# pcb1.net
KiCad netlist of a schematic drawn in EasyEDA Pro
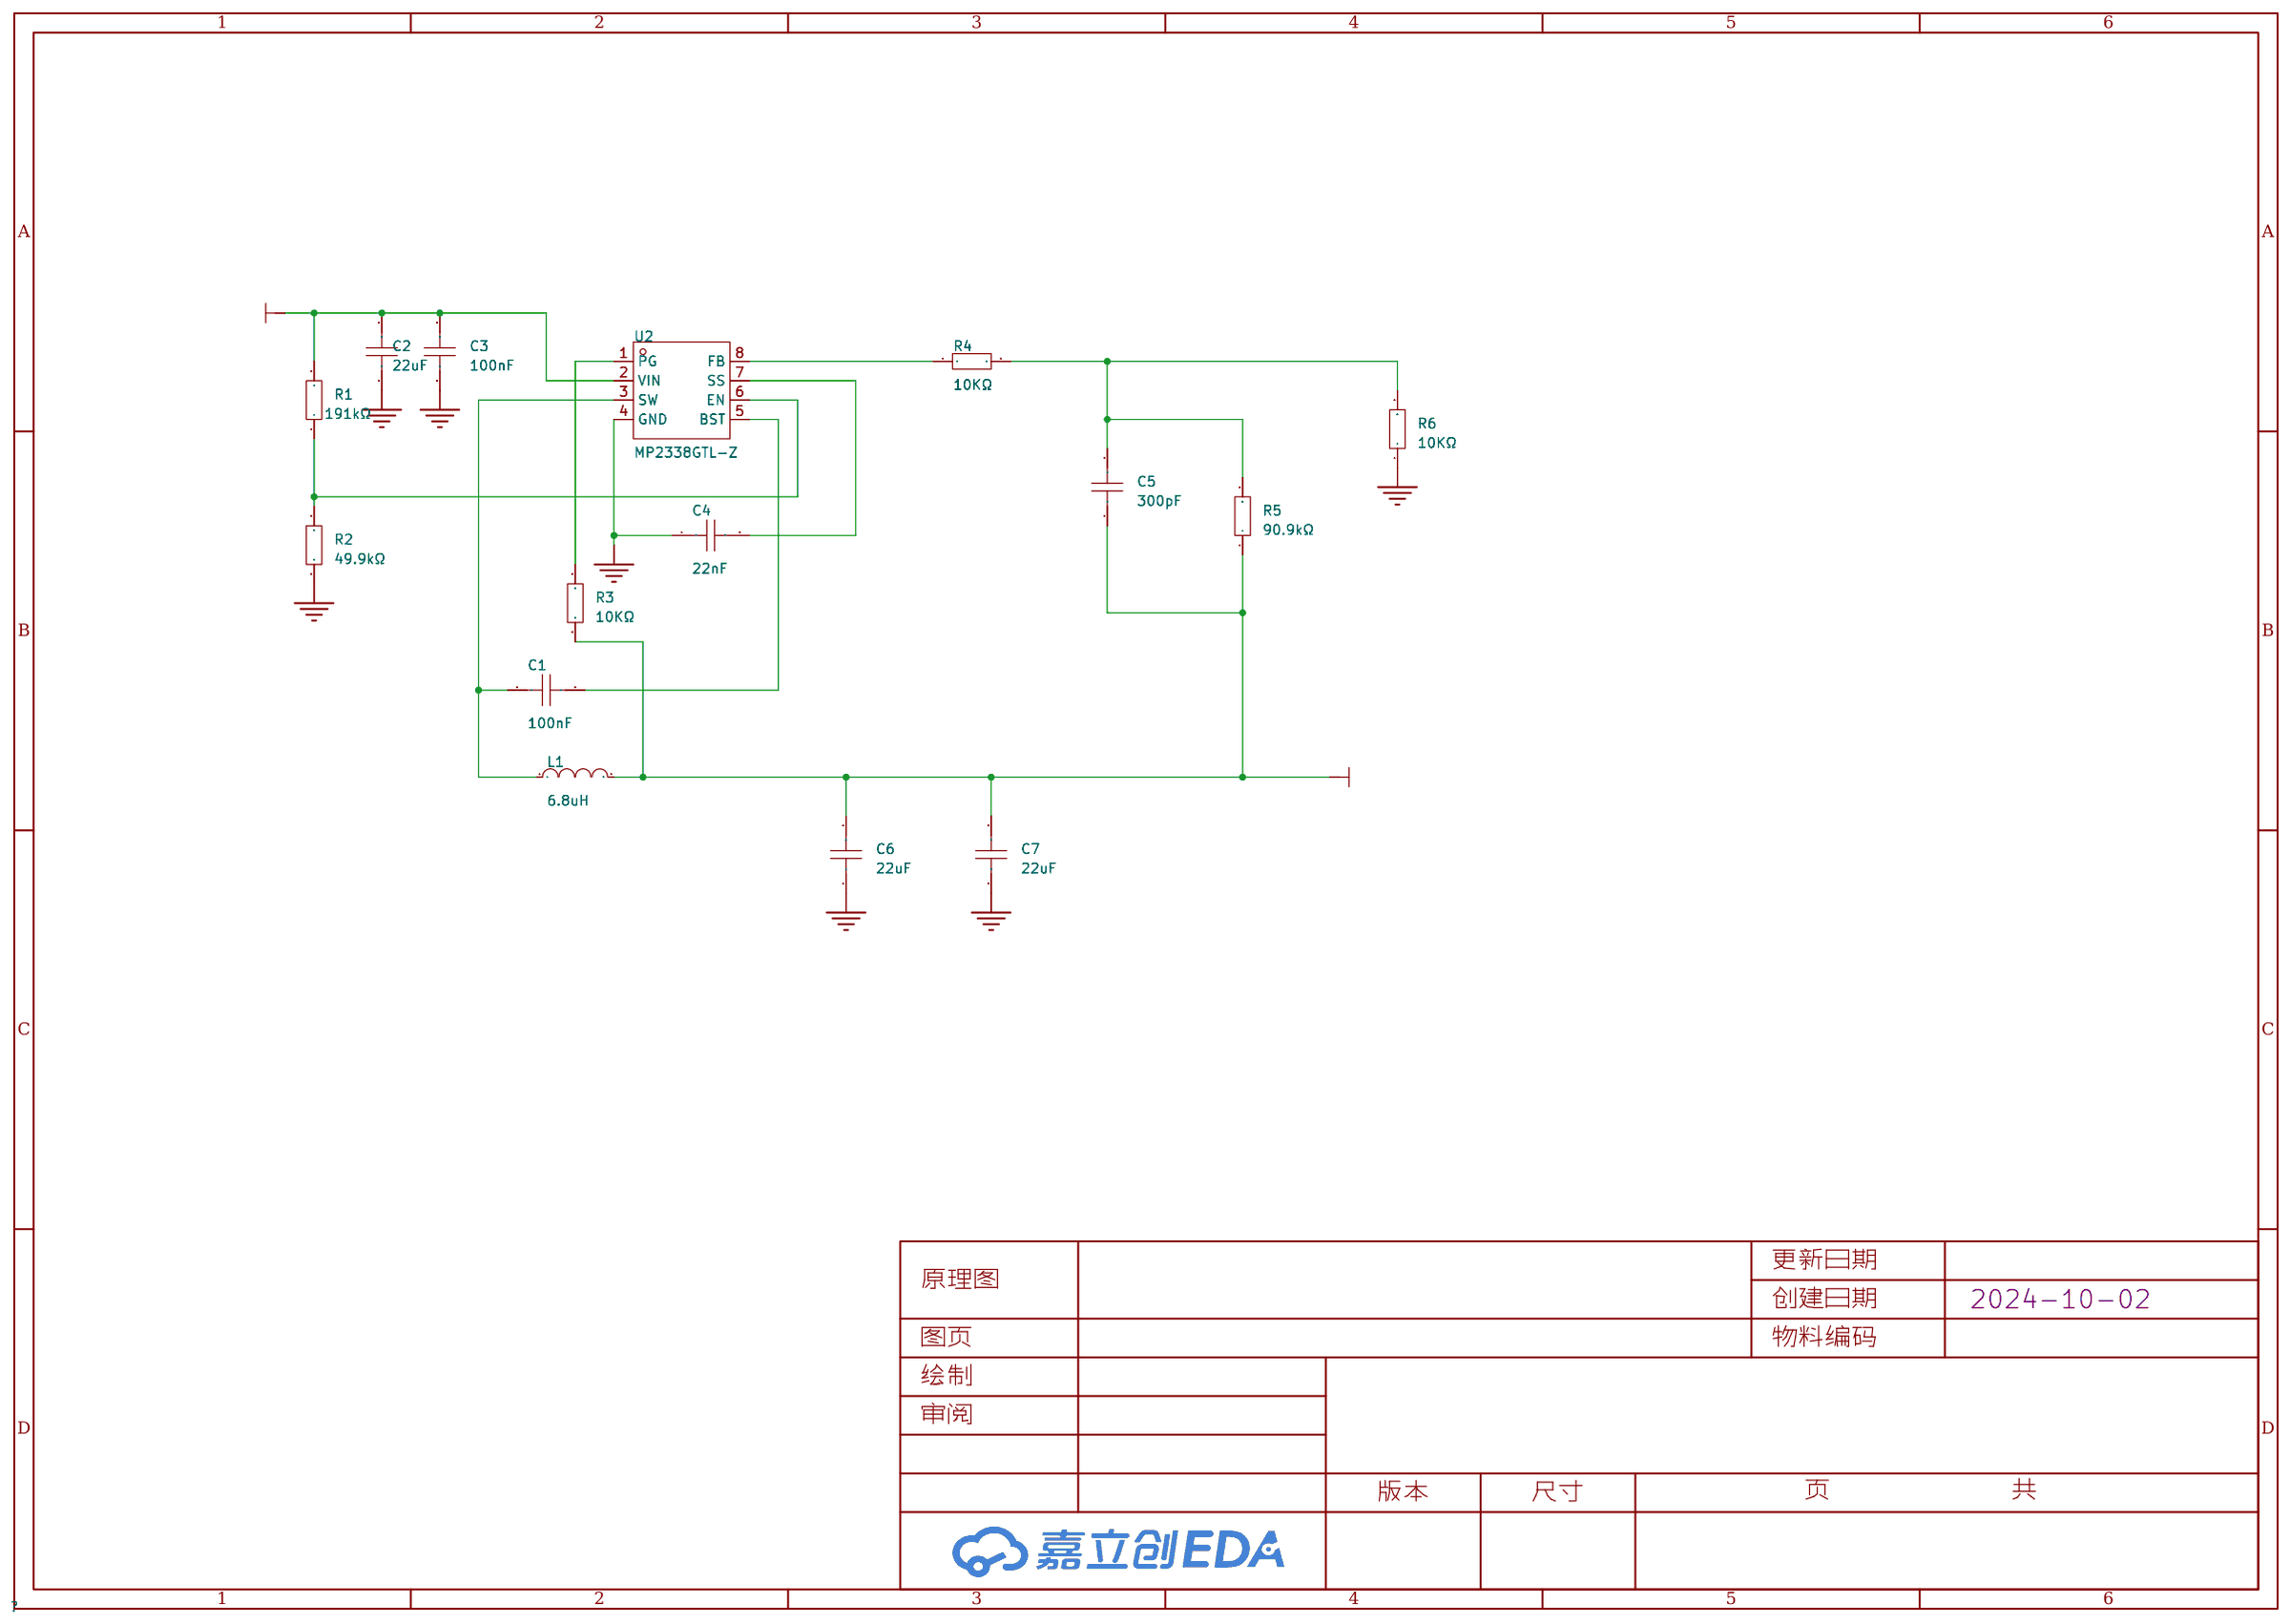
[diagram p0: schematic sheet]

(export (version "E")
  (design (tool "Eeschema 10.0.6"))
  (components
    (comp (ref "C1")
      (value "100nF")
      (footprint "easyedapro:C0603")
      (libsource (lib "easyedapro") (part "CapAcitance"))
    )
    (comp (ref "C2")
      (value "22uF")
      (footprint "easyedapro:C0603")
      (libsource (lib "easyedapro") (part "CapAcitance"))
    )
    (comp (ref "C3")
      (value "100nF")
      (footprint "easyedapro:C0603")
      (libsource (lib "easyedapro") (part "CapAcitance"))
    )
    (comp (ref "C4")
      (value "22nF")
      (footprint "easyedapro:C0603")
      (libsource (lib "easyedapro") (part "CapAcitance"))
    )
    (comp (ref "C5")
      (value "300pF")
      (footprint "easyedapro:C0603")
      (libsource (lib "easyedapro") (part "CapAcitance"))
    )
    (comp (ref "C6")
      (value "22uF")
      (footprint "easyedapro:C0603")
      (libsource (lib "easyedapro") (part "CapAcitance"))
    )
    (comp (ref "C7")
      (value "22uF")
      (footprint "easyedapro:C0603")
      (libsource (lib "easyedapro") (part "CapAcitance"))
    )
    (comp (ref "L1")
      (value "6.8uH")
      (footprint "easyedapro:L0603")
      (libsource (lib "easyedapro") (part "SDFL1608S100KTF"))
    )
    (comp (ref "R1")
      (value "191kΩ")
      (footprint "easyedapro:R0603")
      (libsource (lib "easyedapro") (part "电阻"))
    )
    (comp (ref "R2")
      (value "49.9kΩ")
      (footprint "easyedapro:R0603")
      (libsource (lib "easyedapro") (part "电阻"))
    )
    (comp (ref "R3") (value "10KΩ") (footprint "easyedapro:R0603") (libsource (lib "easyedapro") (part "电阻")))
    (comp (ref "R4") (value "10KΩ") (footprint "easyedapro:R0603") (libsource (lib "easyedapro") (part "电阻")))
    (comp (ref "R5")
      (value "90.9kΩ")
      (footprint "easyedapro:R0603")
      (libsource (lib "easyedapro") (part "电阻"))
    )
    (comp (ref "R6") (value "10KΩ") (footprint "easyedapro:R0603") (libsource (lib "easyedapro") (part "电阻")))
    (comp (ref "U2")
      (value "MP2338GTL-Z")
      (footprint "easyedapro:SOT-583-8_L2.1-W1.2-P0.50-LS1.6-BR")
      (fields (field (name "Manufacturer") "MPS(芯源)"))
      (libsource (lib "easyedapro") (part "mp2338gtl-z_c7210174"))
    )
  )
  (nets
    (net (code "1") (name "GND") (class "Default")
      (node (ref "C2") (pin "1") (pinfunction "1_1") (pintype "input"))
      (node (ref "C3") (pin "1") (pinfunction "1_1") (pintype "input"))
      (node (ref "C4") (pin "1") (pinfunction "1_1") (pintype "input"))
      (node (ref "C6") (pin "1") (pinfunction "1_1") (pintype "input"))
      (node (ref "C7") (pin "1") (pinfunction "1_1") (pintype "input"))
      (node (ref "R2") (pin "1") (pinfunction "1_1") (pintype "input"))
      (node (ref "R6") (pin "1") (pinfunction "1_1") (pintype "input"))
      (node (ref "U2") (pin "4") (pinfunction "GND_4") (pintype "unspecified"))
    )
    (net (code "2") (name "Net-(C5-Pad2)") (class "Default")
      (node (ref "C5") (pin "2") (pinfunction "2_2") (pintype "input"))
      (node (ref "R4") (pin "2") (pinfunction "2_2") (pintype "input"))
      (node (ref "R5") (pin "2") (pinfunction "2_2") (pintype "input"))
      (node (ref "R6") (pin "2") (pinfunction "2_2") (pintype "input"))
    )
    (net (code "3") (name "Net-(U2-BST)") (class "Default")
      (node (ref "C1") (pin "2") (pinfunction "2_2") (pintype "input"))
      (node (ref "U2") (pin "5") (pinfunction "BST_5") (pintype "unspecified"))
    )
    (net (code "4") (name "Net-(U2-EN)") (class "Default")
      (node (ref "R1") (pin "1") (pinfunction "1_1") (pintype "input"))
      (node (ref "R2") (pin "2") (pinfunction "2_2") (pintype "input"))
      (node (ref "U2") (pin "6") (pinfunction "EN_6") (pintype "unspecified"))
    )
    (net (code "5") (name "Net-(U2-FB)") (class "Default")
      (node (ref "R4") (pin "1") (pinfunction "1_1") (pintype "input"))
      (node (ref "U2") (pin "8") (pinfunction "FB_8") (pintype "unspecified"))
    )
    (net (code "6") (name "Net-(U2-PG)") (class "Default")
      (node (ref "R3") (pin "2") (pinfunction "2_2") (pintype "input"))
      (node (ref "U2") (pin "1") (pinfunction "PG_1") (pintype "unspecified"))
    )
    (net (code "7") (name "Net-(U2-SS)") (class "Default")
      (node (ref "C4") (pin "2") (pinfunction "2_2") (pintype "input"))
      (node (ref "U2") (pin "7") (pinfunction "SS_7") (pintype "unspecified"))
    )
    (net (code "8") (name "Net-(U2-SW)") (class "Default")
      (node (ref "C1") (pin "1") (pinfunction "1_1") (pintype "input"))
      (node (ref "L1") (pin "1") (pinfunction "1_1") (pintype "unspecified"))
      (node (ref "U2") (pin "3") (pinfunction "SW_3") (pintype "unspecified"))
    )
    (net (code "9") (name "VIN") (class "Default")
      (node (ref "C2") (pin "2") (pinfunction "2_2") (pintype "input"))
      (node (ref "C3") (pin "2") (pinfunction "2_2") (pintype "input"))
      (node (ref "R1") (pin "2") (pinfunction "2_2") (pintype "input"))
      (node (ref "U2") (pin "2") (pinfunction "VIN_2") (pintype "unspecified"))
    )
    (net (code "10") (name "VOUT") (class "Default")
      (node (ref "C5") (pin "1") (pinfunction "1_1") (pintype "input"))
      (node (ref "C6") (pin "2") (pinfunction "2_2") (pintype "input"))
      (node (ref "C7") (pin "2") (pinfunction "2_2") (pintype "input"))
      (node (ref "L1") (pin "2") (pinfunction "2_2") (pintype "unspecified"))
      (node (ref "R3") (pin "1") (pinfunction "1_1") (pintype "input"))
      (node (ref "R5") (pin "1") (pinfunction "1_1") (pintype "input"))
    )
  )
)
